# CET_GPS_5_03_22.net
KiCad netlist of a schematic drawn in EAGLE
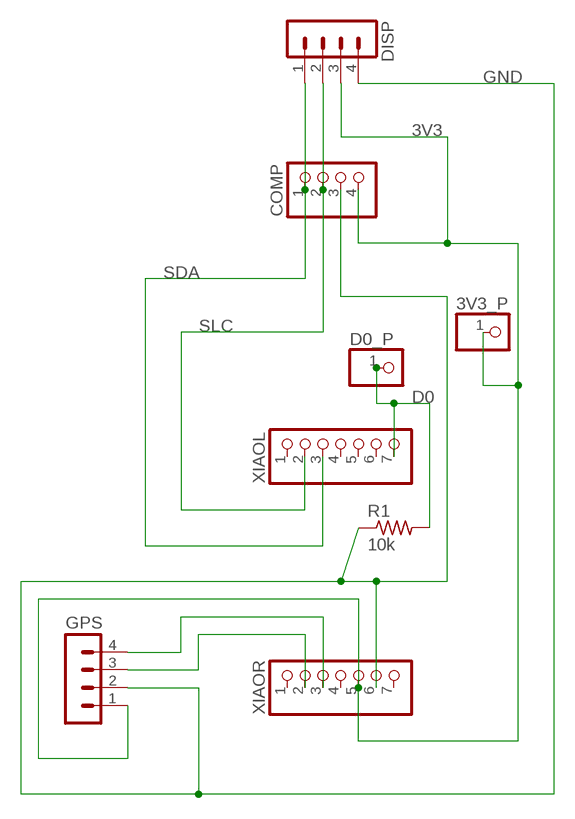
[diagram p0: schematic, sheet 1]

(export (version "E")
  (design (tool "Eeschema 10.0.6"))
  (components
    (comp (ref "3V3_P")
      (value "PINHD-1X1")
      (footprint "eagle-import:1X01")
      (libsource (lib "eagle-import") (part "PINHD-1X1"))
    )
    (comp (ref "COMP")
      (value "PINHD-1X4/90")
      (footprint "eagle-import:1X04_90")
      (libsource (lib "eagle-import") (part "PINHD-1X4/90"))
    )
    (comp (ref "D0_P")
      (value "PINHD-1X1")
      (footprint "eagle-import:1X01")
      (libsource (lib "eagle-import") (part "PINHD-1X1"))
    )
    (comp (ref "DISP")
      (value "MA04-1")
      (footprint "eagle-import:MA04-1")
      (libsource (lib "eagle-import") (part "MA04-1"))
    )
    (comp (ref "GPS")
      (value "MA04-1")
      (footprint "eagle-import:MA04-1")
      (libsource (lib "eagle-import") (part "MA04-1"))
    )
    (comp (ref "R1")
      (value "10k")
      (footprint "eagle-import:0204_7")
      (libsource (lib "eagle-import") (part "R-US_0204/7"))
    )
    (comp (ref "XIAOL")
      (value "PINHD-1X7")
      (footprint "eagle-import:1X07")
      (libsource (lib "eagle-import") (part "PINHD-1X7"))
    )
    (comp (ref "XIAOR")
      (value "PINHD-1X7")
      (footprint "eagle-import:1X07")
      (libsource (lib "eagle-import") (part "PINHD-1X7"))
    )
  )
  (nets
    (net (code "1") (name "/3V3") (class "Default")
      (node (ref "3V3_P") (pin "1") (pinfunction "1_1") (pintype "passive"))
      (node (ref "COMP") (pin "4") (pinfunction "4_4") (pintype "passive"))
      (node (ref "DISP") (pin "3") (pinfunction "3_3") (pintype "passive"))
      (node (ref "GPS") (pin "1") (pinfunction "1_1") (pintype "passive"))
      (node (ref "XIAOR") (pin "5") (pinfunction "5_5") (pintype "passive"))
    )
    (net (code "2") (name "/D0") (class "Default")
      (node (ref "D0_P") (pin "1") (pinfunction "1_1") (pintype "passive"))
      (node (ref "R1") (pin "2") (pinfunction "2_2") (pintype "passive"))
      (node (ref "XIAOL") (pin "7") (pinfunction "7_7") (pintype "passive"))
    )
    (net (code "3") (name "/GND") (class "Default")
      (node (ref "COMP") (pin "3") (pinfunction "3_3") (pintype "passive"))
      (node (ref "DISP") (pin "4") (pinfunction "4_4") (pintype "passive"))
      (node (ref "GPS") (pin "2") (pinfunction "2_2") (pintype "passive"))
      (node (ref "R1") (pin "1") (pinfunction "1_1") (pintype "passive"))
      (node (ref "XIAOR") (pin "6") (pinfunction "6_6") (pintype "passive"))
    )
    (net (code "4") (name "/SDA") (class "Default")
      (node (ref "COMP") (pin "1") (pinfunction "1_1") (pintype "passive"))
      (node (ref "DISP") (pin "1") (pinfunction "1_1") (pintype "passive"))
      (node (ref "XIAOL") (pin "3") (pinfunction "3_3") (pintype "passive"))
    )
    (net (code "5") (name "/SLC") (class "Default")
      (node (ref "COMP") (pin "2") (pinfunction "2_2") (pintype "passive"))
      (node (ref "DISP") (pin "2") (pinfunction "2_2") (pintype "passive"))
      (node (ref "XIAOL") (pin "2") (pinfunction "2_2") (pintype "passive"))
    )
    (net (code "6") (name "Net-(GPS-Pad3)") (class "Default")
      (node (ref "GPS") (pin "3") (pinfunction "3_3") (pintype "passive"))
      (node (ref "XIAOR") (pin "2") (pinfunction "2_2") (pintype "passive"))
    )
    (net (code "7") (name "Net-(GPS-Pad4)") (class "Default")
      (node (ref "GPS") (pin "4") (pinfunction "4_4") (pintype "passive"))
      (node (ref "XIAOR") (pin "3") (pinfunction "3_3") (pintype "passive"))
    )
    (net (code "8") (name "unconnected-(XIAOL-Pad1)") (class "Default")
      (node (ref "XIAOL") (pin "1") (pinfunction "1_1") (pintype "passive"))
    )
    (net (code "9") (name "unconnected-(XIAOL-Pad4)") (class "Default")
      (node (ref "XIAOL") (pin "4") (pinfunction "4_4") (pintype "passive"))
    )
    (net (code "10") (name "unconnected-(XIAOL-Pad5)") (class "Default")
      (node (ref "XIAOL") (pin "5") (pinfunction "5_5") (pintype "passive"))
    )
    (net (code "11") (name "unconnected-(XIAOL-Pad6)") (class "Default")
      (node (ref "XIAOL") (pin "6") (pinfunction "6_6") (pintype "passive"))
    )
    (net (code "12") (name "unconnected-(XIAOR-Pad1)") (class "Default")
      (node (ref "XIAOR") (pin "1") (pinfunction "1_1") (pintype "passive"))
    )
    (net (code "13") (name "unconnected-(XIAOR-Pad4)") (class "Default")
      (node (ref "XIAOR") (pin "4") (pinfunction "4_4") (pintype "passive"))
    )
    (net (code "14") (name "unconnected-(XIAOR-Pad7)") (class "Default")
      (node (ref "XIAOR") (pin "7") (pinfunction "7_7") (pintype "passive"))
    )
  )
)
